# VisualEar-3_0.net
KiCad netlist of a schematic drawn in EAGLE
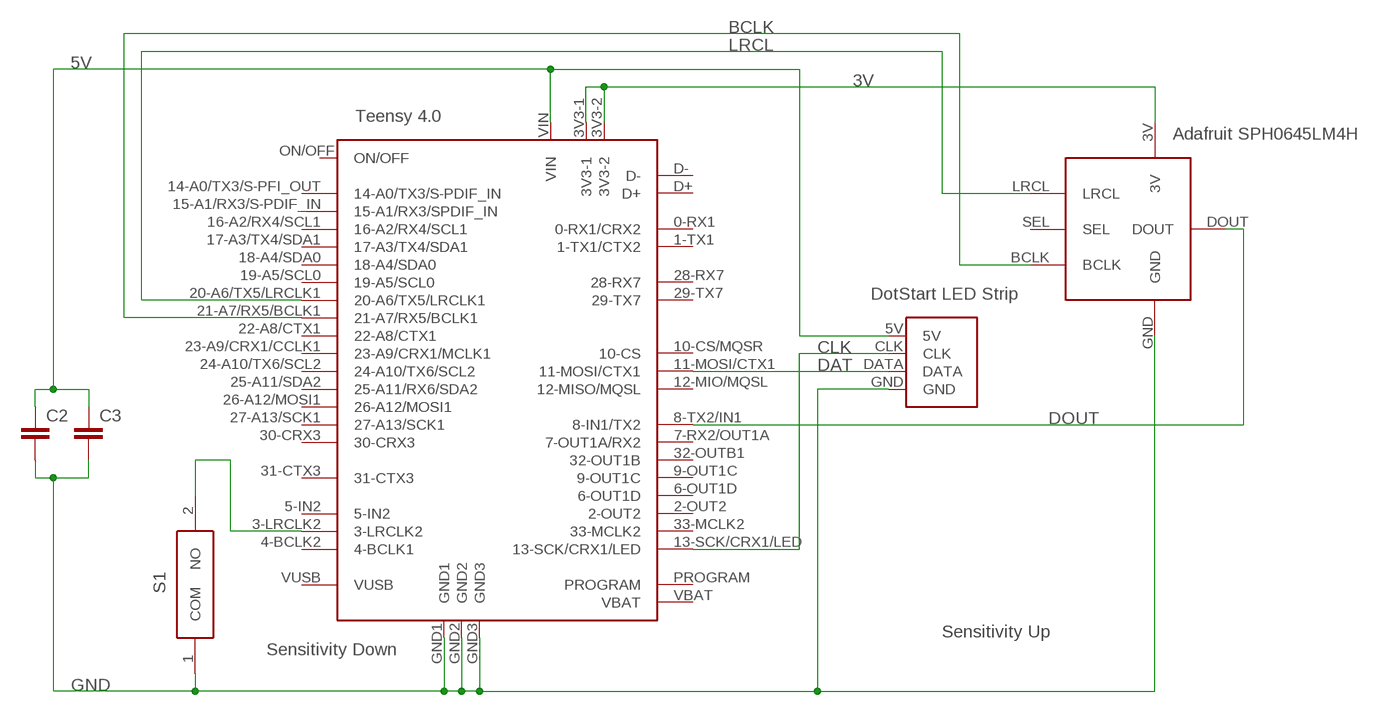
[diagram p0: schematic, sheet 1]

(export (version "E")
  (design (tool "Eeschema 10.0.6"))
  (components
    (comp (ref "C2")
      (value "CAPPTH3")
      (footprint "eagle-import:CAP-PTH-LARGE")
      (libsource (lib "eagle-import") (part "CAPPTH3"))
    )
    (comp (ref "C3")
      (value "CAPPTH3")
      (footprint "eagle-import:CAP-PTH-LARGE")
      (libsource (lib "eagle-import") (part "CAPPTH3"))
    )
    (comp (ref "S1")
      (value "TACTILE-SWITCHTHRU-HOLE")
      (footprint "eagle-import:CLICK-WEL")
      (libsource (lib "eagle-import") (part "TACTILE-SWITCHTHRU-HOLE"))
    )
    (comp (ref "U$1")
      (value "TEENSY40DIPPLUS5")
      (footprint "eagle-import:TEENSY40-DIP+5")
      (libsource (lib "eagle-import") (part "TEENSY40DIPPLUS5"))
    )
    (comp (ref "U$3")
      (value "AF-I2S-MIC")
      (footprint "eagle-import:AF-I2S-MIC")
      (libsource (lib "eagle-import") (part "AF-I2S-MIC"))
    )
    (comp (ref "U$4")
      (value "LED-STRIP")
      (footprint "eagle-import:LED_STRIP")
      (libsource (lib "eagle-import") (part "LED-STRIP"))
    )
  )
  (nets
    (net (code "1") (name "/3V") (class "Default")
      (node (ref "U$1") (pin "3V3-1") (pinfunction "3V3-1_3V3-1") (pintype "bidirectional"))
      (node (ref "U$1") (pin "3V3-2") (pinfunction "3V3-2_3V3-2") (pintype "bidirectional"))
      (node (ref "U$3") (pin "3V") (pinfunction "3V_3V") (pintype "bidirectional"))
    )
    (net (code "2") (name "/5V") (class "Default")
      (node (ref "C2") (pin "1") (pinfunction "1_1") (pintype "passive"))
      (node (ref "C3") (pin "1") (pinfunction "1_1") (pintype "passive"))
      (node (ref "U$1") (pin "VIN") (pinfunction "VIN_VIN") (pintype "bidirectional"))
      (node (ref "U$4") (pin "5V") (pinfunction "5V_5V") (pintype "bidirectional"))
    )
    (net (code "3") (name "/BCLK") (class "Default")
      (node (ref "U$1") (pin "21-A7/RX5/BCLK1") (pinfunction "21-A7/RX5/BCLK1_21-A7/RX5/BCLK1") (pintype "bidirectional"))
      (node (ref "U$3") (pin "BCLK") (pinfunction "BCLK_BCLK") (pintype "bidirectional"))
    )
    (net (code "4") (name "/CLK") (class "Default")
      (node (ref "U$1") (pin "13-SCK/CRX1/LED") (pinfunction "13-SCK/CRX1/LED_13-SCK/CRX1/LED") (pintype "bidirectional"))
      (node (ref "U$4") (pin "CLK") (pinfunction "CLK_CLK") (pintype "bidirectional"))
    )
    (net (code "5") (name "/DAT") (class "Default")
      (node (ref "U$1") (pin "11-MOSI/CTX1") (pinfunction "11-MOSI/CTX1_11-MOSI/CTX1") (pintype "bidirectional"))
      (node (ref "U$4") (pin "DATA") (pinfunction "DATA_DATA") (pintype "bidirectional"))
    )
    (net (code "6") (name "/DOUT") (class "Default")
      (node (ref "U$1") (pin "8-TX2/IN1") (pinfunction "8-IN1/TX2_8-TX2/IN1") (pintype "bidirectional"))
      (node (ref "U$3") (pin "DOUT") (pinfunction "DOUT_DOUT") (pintype "bidirectional"))
    )
    (net (code "7") (name "/GND") (class "Default")
      (node (ref "C2") (pin "2") (pinfunction "2_2") (pintype "passive"))
      (node (ref "C3") (pin "2") (pinfunction "2_2") (pintype "passive"))
      (node (ref "S1") (pin "1") (pinfunction "COM_1") (pintype "bidirectional"))
      (node (ref "U$1") (pin "GND1") (pinfunction "GND1_GND1") (pintype "bidirectional"))
      (node (ref "U$1") (pin "GND2") (pinfunction "GND2_GND2") (pintype "bidirectional"))
      (node (ref "U$1") (pin "GND3") (pinfunction "GND3_GND3") (pintype "bidirectional"))
      (node (ref "U$3") (pin "GND") (pinfunction "GND_GND") (pintype "bidirectional"))
      (node (ref "U$4") (pin "GND") (pinfunction "GND_GND") (pintype "bidirectional"))
    )
    (net (code "8") (name "/LRCL") (class "Default")
      (node (ref "U$1") (pin "20-A6/TX5/LRCLK1") (pinfunction "20-A6/TX5/LRCLK1_20-A6/TX5/LRCLK1") (pintype "bidirectional"))
      (node (ref "U$3") (pin "LRCL") (pinfunction "LRCL_LRCL") (pintype "bidirectional"))
    )
    (net (code "9") (name "Net-(S1-NO)") (class "Default")
      (node (ref "S1") (pin "2") (pinfunction "NO_2") (pintype "bidirectional"))
      (node (ref "U$1") (pin "3-LRCLK2") (pinfunction "3-LRCLK2_3-LRCLK2") (pintype "bidirectional"))
    )
    (net (code "10") (name "unconnected-(U$1-0-RX1{slash}CRX2-Pad0-RX1)") (class "Default")
      (node (ref "U$1") (pin "0-RX1") (pinfunction "0-RX1/CRX2_0-RX1") (pintype "bidirectional"))
    )
    (net (code "11") (name "unconnected-(U$1-1-TX1{slash}CTX2-Pad1-TX1)") (class "Default")
      (node (ref "U$1") (pin "1-TX1") (pinfunction "1-TX1/CTX2_1-TX1") (pintype "bidirectional"))
    )
    (net (code "12") (name "unconnected-(U$1-4-BCLK1-Pad4-BCLK2)") (class "Default")
      (node (ref "U$1") (pin "4-BCLK2") (pinfunction "4-BCLK1_4-BCLK2") (pintype "bidirectional"))
    )
    (net (code "13") (name "unconnected-(U$1-7-OUT1A{slash}RX2-Pad7-RX2{slash}OUT1A)") (class "Default")
      (node (ref "U$1") (pin "7-RX2/OUT1A") (pinfunction "7-OUT1A/RX2_7-RX2/OUT1A") (pintype "bidirectional"))
    )
    (net (code "14") (name "unconnected-(U$1-10-CS-Pad10-CS{slash}MQSR)") (class "Default")
      (node (ref "U$1") (pin "10-CS/MQSR") (pinfunction "10-CS_10-CS/MQSR") (pintype "bidirectional"))
    )
    (net (code "15") (name "unconnected-(U$1-12-MISO{slash}MQSL-Pad12-MIO{slash}MQSL)") (class "Default")
      (node (ref "U$1") (pin "12-MIO/MQSL") (pinfunction "12-MISO/MQSL_12-MIO/MQSL") (pintype "bidirectional"))
    )
    (net (code "16") (name "unconnected-(U$1-14-A0{slash}TX3{slash}S-PDIF_IN-Pad14-A0{slash}TX3{slash}S-PFI_OUT)") (class "Default")
      (node (ref "U$1") (pin "14-A0/TX3/S-PFI_OUT") (pinfunction "14-A0/TX3/S-PDIF_IN_14-A0/TX3/S-PFI_OUT") (pintype "bidirectional"))
    )
    (net (code "17") (name "unconnected-(U$1-15-A1{slash}RX3{slash}SPDIF_IN-Pad15-A1{slash}RX3{slash}S-PDIF_IN)") (class "Default")
      (node (ref "U$1") (pin "15-A1/RX3/S-PDIF_IN") (pinfunction "15-A1/RX3/SPDIF_IN_15-A1/RX3/S-PDIF_IN") (pintype "bidirectional"))
    )
    (net (code "18") (name "unconnected-(U$1-23-A9{slash}CRX1{slash}MCLK1-Pad23-A9{slash}CRX1{slash}CCLK1)") (class "Default")
      (node (ref "U$1") (pin "23-A9/CRX1/CCLK1") (pinfunction "23-A9/CRX1/MCLK1_23-A9/CRX1/CCLK1") (pintype "bidirectional"))
    )
    (net (code "19") (name "unconnected-(U$1-25-A11{slash}RX6{slash}SDA2-Pad25-A11{slash}SDA2)") (class "Default")
      (node (ref "U$1") (pin "25-A11/SDA2") (pinfunction "25-A11/RX6/SDA2_25-A11/SDA2") (pintype "bidirectional"))
    )
    (net (code "20") (name "unconnected-(U$1-32-OUT1B-Pad32-OUTB1)") (class "Default")
      (node (ref "U$1") (pin "32-OUTB1") (pinfunction "32-OUT1B_32-OUTB1") (pintype "bidirectional"))
    )
    (net (code "21") (name "unconnected-(U$1-Pad2-OUT2)") (class "Default")
      (node (ref "U$1") (pin "2-OUT2") (pinfunction "2-OUT2_2-OUT2") (pintype "bidirectional"))
    )
    (net (code "22") (name "unconnected-(U$1-Pad5-IN2)") (class "Default")
      (node (ref "U$1") (pin "5-IN2") (pinfunction "5-IN2_5-IN2") (pintype "bidirectional"))
    )
    (net (code "23") (name "unconnected-(U$1-Pad6-OUT1D)") (class "Default")
      (node (ref "U$1") (pin "6-OUT1D") (pinfunction "6-OUT1D_6-OUT1D") (pintype "bidirectional"))
    )
    (net (code "24") (name "unconnected-(U$1-Pad9-OUT1C)") (class "Default")
      (node (ref "U$1") (pin "9-OUT1C") (pinfunction "9-OUT1C_9-OUT1C") (pintype "bidirectional"))
    )
    (net (code "25") (name "unconnected-(U$1-Pad16-A2{slash}RX4{slash}SCL1)") (class "Default")
      (node (ref "U$1") (pin "16-A2/RX4/SCL1") (pinfunction "16-A2/RX4/SCL1_16-A2/RX4/SCL1") (pintype "bidirectional"))
    )
    (net (code "26") (name "unconnected-(U$1-Pad17-A3{slash}TX4{slash}SDA1)") (class "Default")
      (node (ref "U$1") (pin "17-A3/TX4/SDA1") (pinfunction "17-A3/TX4/SDA1_17-A3/TX4/SDA1") (pintype "bidirectional"))
    )
    (net (code "27") (name "unconnected-(U$1-Pad18-A4{slash}SDA0)") (class "Default")
      (node (ref "U$1") (pin "18-A4/SDA0") (pinfunction "18-A4/SDA0_18-A4/SDA0") (pintype "bidirectional"))
    )
    (net (code "28") (name "unconnected-(U$1-Pad19-A5{slash}SCL0)") (class "Default")
      (node (ref "U$1") (pin "19-A5/SCL0") (pinfunction "19-A5/SCL0_19-A5/SCL0") (pintype "bidirectional"))
    )
    (net (code "29") (name "unconnected-(U$1-Pad22-A8{slash}CTX1)") (class "Default")
      (node (ref "U$1") (pin "22-A8/CTX1") (pinfunction "22-A8/CTX1_22-A8/CTX1") (pintype "bidirectional"))
    )
    (net (code "30") (name "unconnected-(U$1-Pad24-A10{slash}TX6{slash}SCL2)") (class "Default")
      (node (ref "U$1") (pin "24-A10/TX6/SCL2") (pinfunction "24-A10/TX6/SCL2_24-A10/TX6/SCL2") (pintype "bidirectional"))
    )
    (net (code "31") (name "unconnected-(U$1-Pad26-A12{slash}MOSI1)") (class "Default")
      (node (ref "U$1") (pin "26-A12/MOSI1") (pinfunction "26-A12/MOSI1_26-A12/MOSI1") (pintype "bidirectional"))
    )
    (net (code "32") (name "unconnected-(U$1-Pad27-A13{slash}SCK1)") (class "Default")
      (node (ref "U$1") (pin "27-A13/SCK1") (pinfunction "27-A13/SCK1_27-A13/SCK1") (pintype "bidirectional"))
    )
    (net (code "33") (name "unconnected-(U$1-Pad28-RX7)") (class "Default")
      (node (ref "U$1") (pin "28-RX7") (pinfunction "28-RX7_28-RX7") (pintype "bidirectional"))
    )
    (net (code "34") (name "unconnected-(U$1-Pad29-TX7)") (class "Default")
      (node (ref "U$1") (pin "29-TX7") (pinfunction "29-TX7_29-TX7") (pintype "bidirectional"))
    )
    (net (code "35") (name "unconnected-(U$1-Pad30-CRX3)") (class "Default")
      (node (ref "U$1") (pin "30-CRX3") (pinfunction "30-CRX3_30-CRX3") (pintype "bidirectional"))
    )
    (net (code "36") (name "unconnected-(U$1-Pad31-CTX3)") (class "Default")
      (node (ref "U$1") (pin "31-CTX3") (pinfunction "31-CTX3_31-CTX3") (pintype "bidirectional"))
    )
    (net (code "37") (name "unconnected-(U$1-Pad33-MCLK2)") (class "Default")
      (node (ref "U$1") (pin "33-MCLK2") (pinfunction "33-MCLK2_33-MCLK2") (pintype "bidirectional"))
    )
    (net (code "38") (name "unconnected-(U$1-PadD+)") (class "Default")
      (node (ref "U$1") (pin "D+") (pinfunction "D+_D+") (pintype "bidirectional"))
    )
    (net (code "39") (name "unconnected-(U$1-PadD-)") (class "Default")
      (node (ref "U$1") (pin "D-") (pinfunction "D-_D-") (pintype "bidirectional"))
    )
    (net (code "40") (name "unconnected-(U$1-PadON{slash}OFF)") (class "Default")
      (node (ref "U$1") (pin "ON/OFF") (pinfunction "ON/OFF_ON/OFF") (pintype "bidirectional"))
    )
    (net (code "41") (name "unconnected-(U$1-PadPROGRAM)") (class "Default")
      (node (ref "U$1") (pin "PROGRAM") (pinfunction "PROGRAM_PROGRAM") (pintype "bidirectional"))
    )
    (net (code "42") (name "unconnected-(U$1-PadVBAT)") (class "Default")
      (node (ref "U$1") (pin "VBAT") (pinfunction "VBAT_VBAT") (pintype "bidirectional"))
    )
    (net (code "43") (name "unconnected-(U$1-PadVUSB)") (class "Default")
      (node (ref "U$1") (pin "VUSB") (pinfunction "VUSB_VUSB") (pintype "bidirectional"))
    )
    (net (code "44") (name "unconnected-(U$3-PadSEL)") (class "Default")
      (node (ref "U$3") (pin "SEL") (pinfunction "SEL_SEL") (pintype "bidirectional"))
    )
  )
)
